# Power.net
KiCad netlist of a schematic drawn in Altium Designer
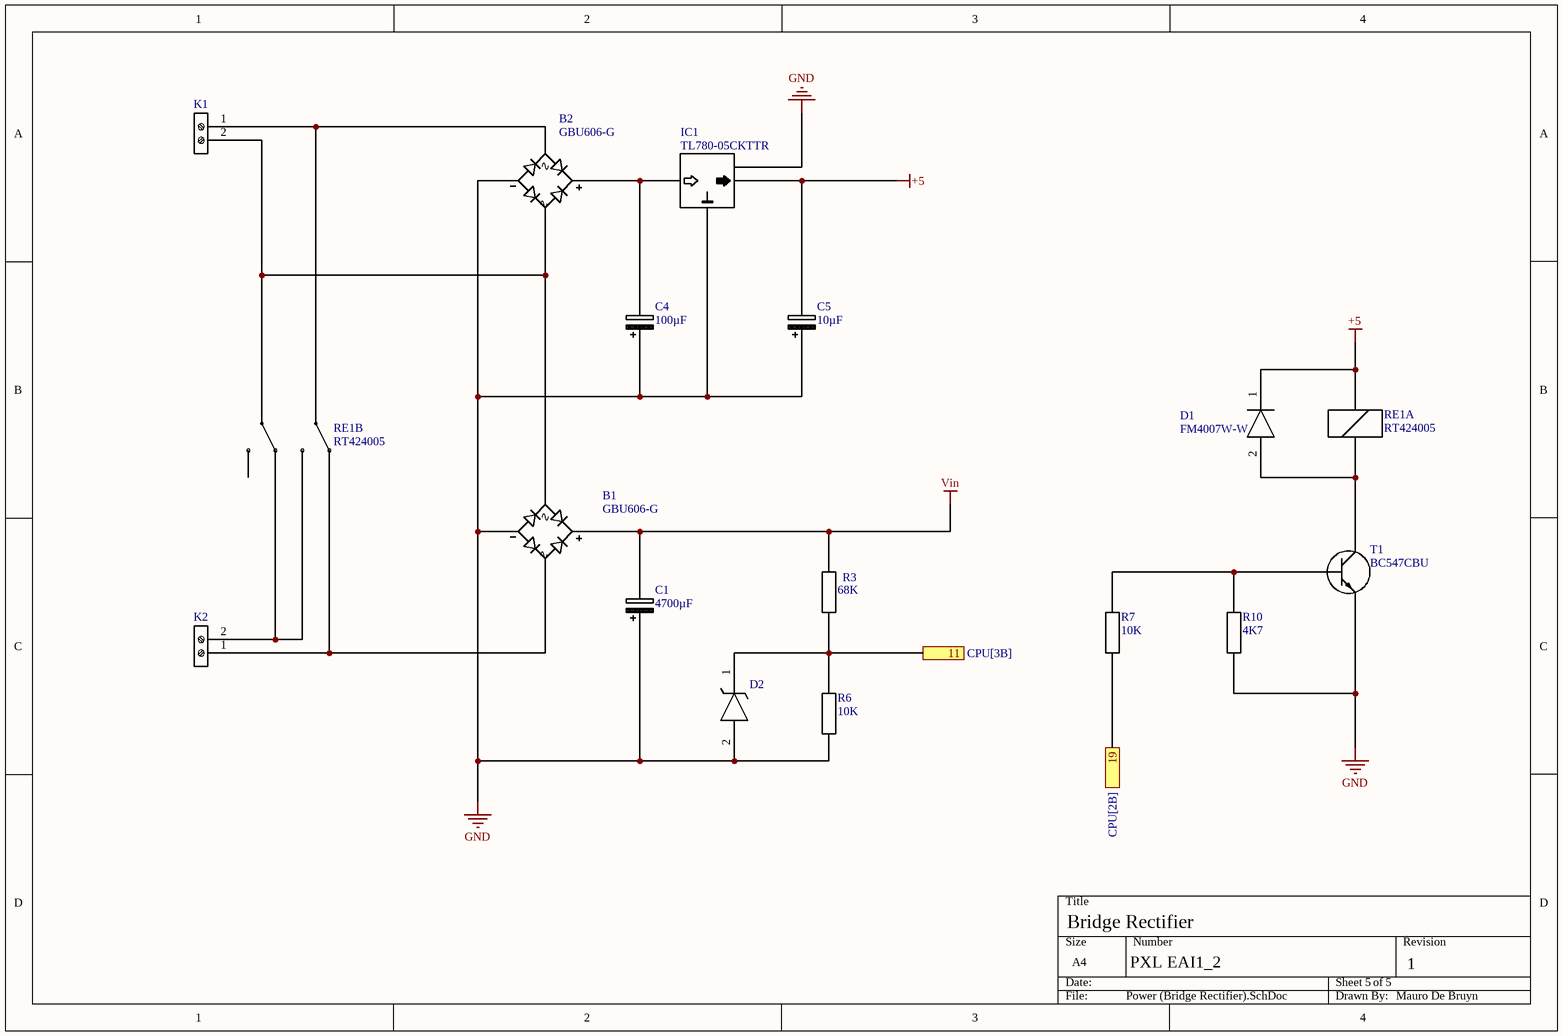
[diagram p0: Power (Bridge Rectifier).SchDoc]

(export (version "E")
  (design (tool "Eeschema 10.0.6"))
  (components
    (comp (ref "B1")
      (value "GBU606-G")
      (footprint "SamacSys:GBU606G")
      (description "Bridge Rectifier")
      (libsource (lib "SamacSys") (part "GBU606-G"))
    )
    (comp (ref "B2")
      (value "GBU606-G")
      (footprint "SamacSys:GBU606G")
      (description "Bridge Rectifier")
      (libsource (lib "SamacSys") (part "GBU606-G"))
    )
    (comp (ref "C1")
      (value "4700µF")
      (footprint "SamacSys:CAPPRD750W80D1850H4150")
      (description "Capacitor Polarised")
      (fields
        (field (name "MOUSER2 PART NUMBER") "232-50PK4700MEFC18X4")
        (field (name "MANUFACTURER_PART_NUMBER") "50PK4700MEFC18X40")
      )
      (libsource (lib "SamacSys") (part "50PK4700MEFC18X40"))
    )
    (comp (ref "C4")
      (value "100µF")
      (footprint "SamacSys:CAPPRD350W60D825H1300")
      (description "Capacitor Polarised")
      (fields (field (name "MANUFACTURER_PART_NUMBER") "RGA101M1HBK-0811G"))
      (libsource (lib "SamacSys") (part "RGA101M1HBK-0811G"))
    )
    (comp (ref "C5")
      (value "10µF")
      (footprint "SamacSys:CAPPRD200W52D500H1250")
      (description "Capacitor Polarised")
      (fields
        (field (name "MOUSER2 PART NUMBER") "710-860020672010")
        (field (name "MANUFACTURER_PART_NUMBER") "860020672010")
      )
      (libsource (lib "SamacSys") (part "860020672010"))
    )
    (comp (ref "D1")
      (value "FM4007W-W")
      (footprint "SamacSys:DIOM5025X231N")
      (description "Bridge Rectifier")
      (fields (field (name "MOUSER2 PART NUMBER") "583-FM4007W-W"))
      (libsource (lib "SamacSys") (part "FM4007W-W"))
    )
    (comp (ref "D2")
      (value "SZMMSZ5231BT1G")
      (footprint "SamacSys:SOD3716X135N")
      (description "Zener Diode")
      (fields (field (name "MOUSER PART NUMBER") "863-SZMMSZ5231BT1G"))
      (libsource (lib "SamacSys") (part "SZMMSZ5231BT1G"))
    )
    (comp (ref "IC1")
      (value "TL780-05CKTTR")
      (footprint "SamacSys:TL78005CKTTR")
      (description "Integrated Circuit")
      (libsource (lib "SamacSys") (part "TL780-05CKTTR"))
    )
    (comp (ref "K1")
      (value "2 Pin Connector 1716020000")
      (footprint "SamacSys:1716020000")
      (description "Connector")
      (fields (field (name "MANUFACTURER_PART_NUMBER") "1716020000"))
      (libsource (lib "SamacSys") (part "2 Pin Connector 1716020000"))
    )
    (comp (ref "K2")
      (value "2 Pin Connector 1716020000")
      (footprint "SamacSys:1716020000")
      (description "Connector")
      (fields (field (name "MANUFACTURER_PART_NUMBER") "1716020000"))
      (libsource (lib "") (part "2 Pin Connector 1716020000_1"))
    )
    (comp (ref "R3")
      (value "68K")
      (footprint "0805")
      (description "Resistor")
      (fields (field (name "MANUFACTURER_PART_NUMBER") "C0805C391G3GACTU"))
      (libsource (lib "SamacSys") (part "0805 (Resistor)"))
    )
    (comp (ref "R6")
      (value "10K")
      (footprint "0805")
      (description "Resistor")
      (fields (field (name "MANUFACTURER_PART_NUMBER") "C0805C391G3GACTU"))
      (libsource (lib "SamacSys") (part "0805 (Resistor)"))
    )
    (comp (ref "R7")
      (value "10K")
      (footprint "0805")
      (description "Resistor")
      (fields (field (name "MANUFACTURER_PART_NUMBER") "C0805C391G3GACTU"))
      (libsource (lib "SamacSys") (part "0805 (Resistor)"))
    )
    (comp (ref "R10")
      (value "4K7")
      (footprint "0805")
      (description "Resistor")
      (fields (field (name "MANUFACTURER_PART_NUMBER") "C0805C391G3GACTU"))
      (libsource (lib "SamacSys") (part "0805 (Resistor)"))
    )
    (comp (ref "RE1")
      (value "RT424005")
      (footprint "SamacSys:RT42")
      (description "Relay or Contactor")
      (fields (field (name "MOUSER2 PART NUMBER") "655-RT424005"))
      (libsource (lib "SamacSys") (part "RT424005"))
    )
    (comp (ref "T1")
      (value "BC547CBU")
      (footprint "SamacSys:BC547CBU")
      (description "Transistor BJT NPN")
      (libsource (lib "SamacSys") (part "BC547CBU"))
    )
  )
  (nets
    (net (code "1") (name "+5") (class "Default")
      (node (ref "C5") (pin "2") (pinfunction "-_2") (pintype "passive"))
      (node (ref "D1") (pin "1") (pinfunction "K_1") (pintype "passive"))
      (node (ref "IC1") (pin "3") (pinfunction "OUTPUT_3") (pintype "passive"))
      (node (ref "RE1") (pin "1") (pinfunction "A1_COIL_1") (pintype "passive"))
    )
    (net (code "2") (name "/11") (class "Default")
      (node (ref "D2") (pin "1") (pinfunction "K_1") (pintype "passive"))
      (node (ref "R3") (pin "1") (pinfunction "1_1") (pintype "passive"))
      (node (ref "R6") (pin "2") (pinfunction "2_2") (pintype "passive"))
    )
    (net (code "3") (name "/19") (class "Default")
      (node (ref "R7") (pin "2") (pinfunction "2_2") (pintype "passive"))
    )
    (net (code "4") (name "GND") (class "Default")
      (node (ref "B1") (pin "4") (pinfunction "-_4") (pintype "passive"))
      (node (ref "B2") (pin "4") (pinfunction "-_4") (pintype "passive"))
      (node (ref "C1") (pin "1") (pinfunction "+_1") (pintype "passive"))
      (node (ref "C4") (pin "1") (pinfunction "+_1") (pintype "passive"))
      (node (ref "C5") (pin "1") (pinfunction "+_1") (pintype "passive"))
      (node (ref "D2") (pin "2") (pinfunction "A_2") (pintype "passive"))
      (node (ref "IC1") (pin "2") (pinfunction "COMMON_1_2") (pintype "passive"))
      (node (ref "IC1") (pin "4") (pinfunction "COMMON_2_4") (pintype "passive"))
      (node (ref "R10") (pin "2") (pinfunction "2_2") (pintype "passive"))
      (node (ref "R6") (pin "1") (pinfunction "1_1") (pintype "passive"))
      (node (ref "T1") (pin "3") (pinfunction "E_3") (pintype "passive"))
    )
    (net (code "5") (name "Net-(B1-~_1)") (class "Default")
      (node (ref "B1") (pin "2") (pinfunction "~_1_2") (pintype "passive"))
      (node (ref "K2") (pin "1") (pinfunction "1_1") (pintype "passive"))
      (node (ref "RE1") (pin "7") (pinfunction "22_NC_7") (pintype "passive"))
    )
    (net (code "6") (name "Net-(B1-~_2)") (class "Default")
      (node (ref "B1") (pin "3") (pinfunction "~_2_3") (pintype "passive"))
      (node (ref "B2") (pin "2") (pinfunction "~_1_2") (pintype "passive"))
      (node (ref "K1") (pin "2") (pinfunction "2_2") (pintype "passive"))
      (node (ref "RE1") (pin "3") (pinfunction "11_COM_3") (pintype "passive"))
    )
    (net (code "7") (name "Net-(B2-+)") (class "Default")
      (node (ref "B2") (pin "1") (pinfunction "+_1") (pintype "passive"))
      (node (ref "C4") (pin "2") (pinfunction "-_2") (pintype "passive"))
      (node (ref "IC1") (pin "1") (pinfunction "INPUT_1") (pintype "passive"))
    )
    (net (code "8") (name "Net-(B2-~_2)") (class "Default")
      (node (ref "B2") (pin "3") (pinfunction "~_2_3") (pintype "passive"))
      (node (ref "K1") (pin "1") (pinfunction "1_1") (pintype "passive"))
      (node (ref "RE1") (pin "6") (pinfunction "21_COM_6") (pintype "passive"))
    )
    (net (code "9") (name "Net-(D1-A)") (class "Default")
      (node (ref "D1") (pin "2") (pinfunction "A_2") (pintype "passive"))
      (node (ref "RE1") (pin "8") (pinfunction "A2_COIL_8") (pintype "passive"))
      (node (ref "T1") (pin "1") (pinfunction "C_1") (pintype "passive"))
    )
    (net (code "10") (name "Net-(RE1B-12_NC)") (class "Default")
      (node (ref "K2") (pin "2") (pinfunction "2_2") (pintype "passive"))
      (node (ref "RE1") (pin "2") (pinfunction "12_NC_2") (pintype "passive"))
      (node (ref "RE1") (pin "5") (pinfunction "24_NO_5") (pintype "passive"))
    )
    (net (code "11") (name "Net-(T1-B)") (class "Default")
      (node (ref "R10") (pin "1") (pinfunction "1_1") (pintype "passive"))
      (node (ref "R7") (pin "1") (pinfunction "1_1") (pintype "passive"))
      (node (ref "T1") (pin "2") (pinfunction "B_2") (pintype "passive"))
    )
    (net (code "12") (name "Vin") (class "Default")
      (node (ref "B1") (pin "1") (pinfunction "+_1") (pintype "passive"))
      (node (ref "C1") (pin "2") (pinfunction "-_2") (pintype "passive"))
      (node (ref "R3") (pin "2") (pinfunction "2_2") (pintype "passive"))
    )
    (net (code "13") (name "unconnected-(RE1B-14_NO-Pad4)") (class "Default")
      (node (ref "RE1") (pin "4") (pinfunction "14_NO_4") (pintype "passive"))
    )
  )
)
